# prototipo_final_2_1.net
KiCad netlist of a schematic drawn in EAGLE
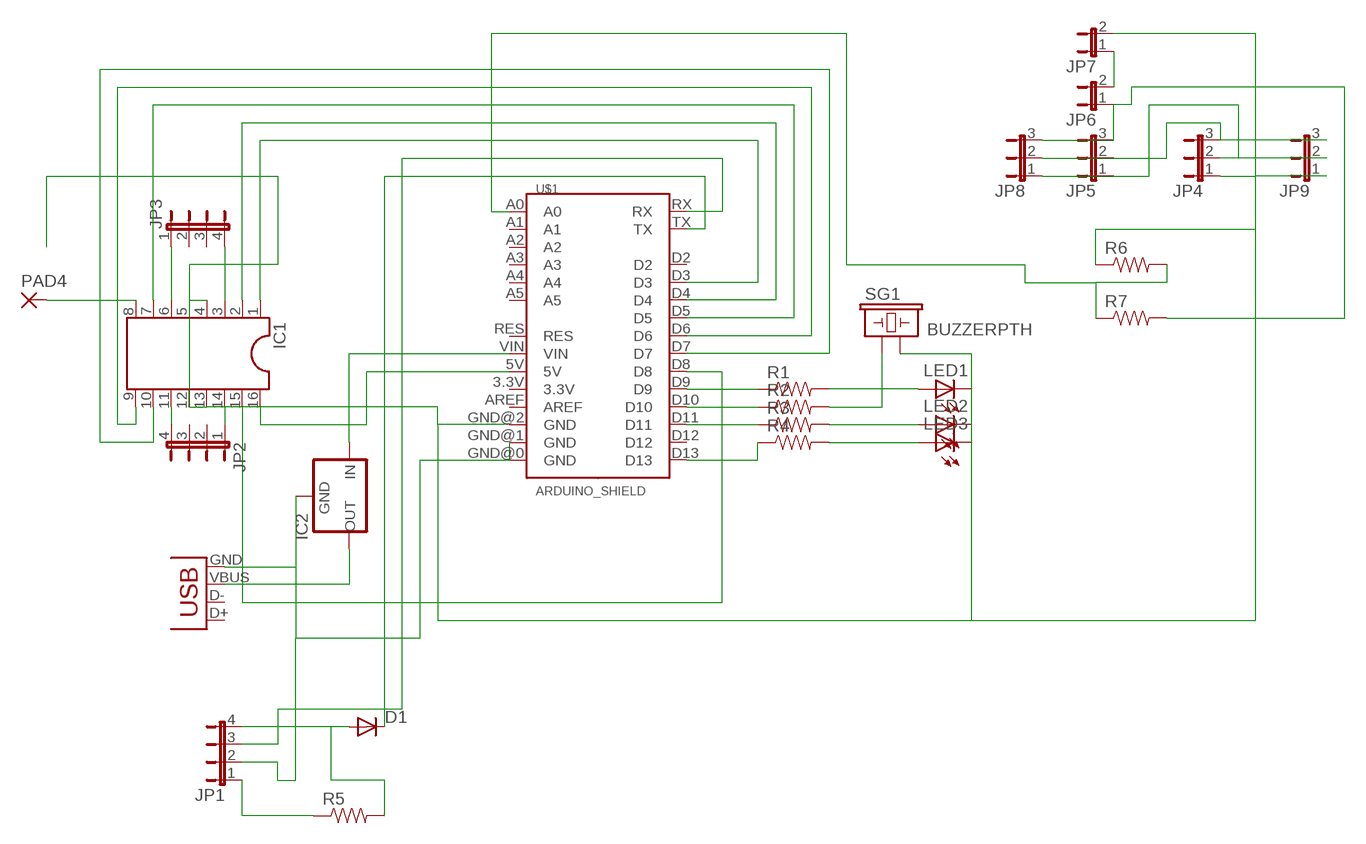
[diagram p0: schematic, sheet 1]

(export (version "E")
  (design (tool "Eeschema 10.0.6"))
  (components
    (comp (ref "D1")
      (value "DIODEPTH")
      (footprint "eagle-import:DIODE-1N4001")
      (libsource (lib "eagle-import") (part "DIODEPTH"))
    )
    (comp (ref "IC1")
      (value "DIL16S")
      (footprint "eagle-import:SOCKET-16")
      (libsource (lib "eagle-import") (part "DIL16S"))
    )
    (comp (ref "IC2")
      (value "V_REG_78XXSINK")
      (footprint "eagle-import:TO220-IGO")
      (libsource (lib "eagle-import") (part "V_REG_78XXSINK"))
    )
    (comp (ref "JP1")
      (value "JP4E")
      (footprint "eagle-import:JP4")
      (libsource (lib "eagle-import") (part "JP4E"))
    )
    (comp (ref "JP2")
      (value "JP4E")
      (footprint "eagle-import:JP4")
      (libsource (lib "eagle-import") (part "JP4E"))
    )
    (comp (ref "JP3")
      (value "JP4E")
      (footprint "eagle-import:JP4")
      (libsource (lib "eagle-import") (part "JP4E"))
    )
    (comp (ref "JP4")
      (value "JP2E")
      (footprint "eagle-import:JP2")
      (libsource (lib "eagle-import") (part "JP2E"))
    )
    (comp (ref "JP5")
      (value "JP2E")
      (footprint "eagle-import:JP2")
      (libsource (lib "eagle-import") (part "JP2E"))
    )
    (comp (ref "JP6")
      (value "JP1E")
      (footprint "eagle-import:JP1")
      (libsource (lib "eagle-import") (part "JP1E"))
    )
    (comp (ref "JP7")
      (value "JP1E")
      (footprint "eagle-import:JP1")
      (libsource (lib "eagle-import") (part "JP1E"))
    )
    (comp (ref "JP8")
      (value "JP2E")
      (footprint "eagle-import:JP2")
      (libsource (lib "eagle-import") (part "JP2E"))
    )
    (comp (ref "JP9")
      (value "JP2E")
      (footprint "eagle-import:JP2")
      (libsource (lib "eagle-import") (part "JP2E"))
    )
    (comp (ref "LED1")
      (value "LED3MM")
      (footprint "eagle-import:LED3MM")
      (libsource (lib "eagle-import") (part "LED3MM"))
    )
    (comp (ref "LED2")
      (value "LED3MM")
      (footprint "eagle-import:LED3MM")
      (libsource (lib "eagle-import") (part "LED3MM"))
    )
    (comp (ref "LED3")
      (value "LED3MM")
      (footprint "eagle-import:LED3MM")
      (libsource (lib "eagle-import") (part "LED3MM"))
    )
    (comp (ref "PAD4")
      (value "2,15/1,0")
      (footprint "eagle-import:2,15_1,0")
      (libsource (lib "eagle-import") (part "2,15/1,0"))
    )
    (comp (ref "R1")
      (value "RESISTORPTH1")
      (footprint "eagle-import:AXIAL-0.3")
      (libsource (lib "eagle-import") (part "RESISTORPTH1"))
    )
    (comp (ref "R2")
      (value "RESISTORPTH1")
      (footprint "eagle-import:AXIAL-0.3")
      (libsource (lib "eagle-import") (part "RESISTORPTH1"))
    )
    (comp (ref "R3")
      (value "RESISTORPTH1")
      (footprint "eagle-import:AXIAL-0.3")
      (libsource (lib "eagle-import") (part "RESISTORPTH1"))
    )
    (comp (ref "R4")
      (value "RESISTORPTH1")
      (footprint "eagle-import:AXIAL-0.3")
      (libsource (lib "eagle-import") (part "RESISTORPTH1"))
    )
    (comp (ref "R5")
      (value "RESISTORPTH1")
      (footprint "eagle-import:AXIAL-0.3")
      (libsource (lib "eagle-import") (part "RESISTORPTH1"))
    )
    (comp (ref "R6")
      (value "RESISTORPTH1")
      (footprint "eagle-import:AXIAL-0.3")
      (libsource (lib "eagle-import") (part "RESISTORPTH1"))
    )
    (comp (ref "R7")
      (value "RESISTORPTH1")
      (footprint "eagle-import:AXIAL-0.3")
      (libsource (lib "eagle-import") (part "RESISTORPTH1"))
    )
    (comp (ref "SG1")
      (value "BUZZERPTH")
      (footprint "eagle-import:BUZZER-12MM")
      (libsource (lib "eagle-import") (part "BUZZERPTH"))
    )
    (comp (ref "U$1")
      (value "ARDUINO_SHIELD")
      (footprint "eagle-import:DUEMILANOVE_SHIELD")
      (libsource (lib "eagle-import") (part "ARDUINO_SHIELD"))
    )
    (comp (ref "X1")
      (value "USB-A-S")
      (footprint "eagle-import:USB-A-S")
      (libsource (lib "eagle-import") (part "USB-A-S"))
    )
  )
  (nets
    (net (code "1") (name "Net-(D1-PadC)") (class "Default")
      (node (ref "D1") (pin "C") (pinfunction "C_C") (pintype "passive"))
      (node (ref "U$1") (pin "TX") (pinfunction "TX_TX") (pintype "bidirectional"))
    )
    (net (code "2") (name "Net-(IC1-Pad1)") (class "Default")
      (node (ref "IC1") (pin "1") (pinfunction "1_1") (pintype "passive"))
      (node (ref "U$1") (pin "D3") (pinfunction "D3_D3") (pintype "bidirectional"))
    )
    (net (code "3") (name "Net-(IC1-Pad2)") (class "Default")
      (node (ref "IC1") (pin "2") (pinfunction "2_2") (pintype "passive"))
      (node (ref "U$1") (pin "D4") (pinfunction "D4_D4") (pintype "bidirectional"))
    )
    (net (code "4") (name "Net-(IC1-Pad3)") (class "Default")
      (node (ref "IC1") (pin "3") (pinfunction "3_3") (pintype "passive"))
      (node (ref "JP3") (pin "4") (pinfunction "4_4") (pintype "passive"))
    )
    (net (code "5") (name "Net-(IC1-Pad6)") (class "Default")
      (node (ref "IC1") (pin "6") (pinfunction "6_6") (pintype "passive"))
      (node (ref "JP3") (pin "1") (pinfunction "1_1") (pintype "passive"))
    )
    (net (code "6") (name "Net-(IC1-Pad7)") (class "Default")
      (node (ref "IC1") (pin "7") (pinfunction "7_7") (pintype "passive"))
      (node (ref "U$1") (pin "D5") (pinfunction "D5_D5") (pintype "bidirectional"))
    )
    (net (code "7") (name "Net-(IC1-Pad9)") (class "Default")
      (node (ref "IC1") (pin "9") (pinfunction "9_9") (pintype "passive"))
      (node (ref "U$1") (pin "D6") (pinfunction "D6_D6") (pintype "bidirectional"))
    )
    (net (code "8") (name "Net-(IC1-Pad10)") (class "Default")
      (node (ref "IC1") (pin "10") (pinfunction "10_10") (pintype "passive"))
      (node (ref "U$1") (pin "D7") (pinfunction "D7_D7") (pintype "bidirectional"))
    )
    (net (code "9") (name "Net-(IC1-Pad11)") (class "Default")
      (node (ref "IC1") (pin "11") (pinfunction "11_11") (pintype "passive"))
      (node (ref "JP2") (pin "4") (pinfunction "4_4") (pintype "passive"))
    )
    (net (code "10") (name "Net-(IC1-Pad14)") (class "Default")
      (node (ref "IC1") (pin "14") (pinfunction "14_14") (pintype "passive"))
      (node (ref "JP2") (pin "1") (pinfunction "1_1") (pintype "passive"))
    )
    (net (code "11") (name "Net-(IC1-Pad15)") (class "Default")
      (node (ref "IC1") (pin "15") (pinfunction "15_15") (pintype "passive"))
      (node (ref "U$1") (pin "D8") (pinfunction "D8_D8") (pintype "bidirectional"))
    )
    (net (code "12") (name "Net-(IC1-Pad16)") (class "Default")
      (node (ref "IC1") (pin "16") (pinfunction "16_16") (pintype "passive"))
      (node (ref "U$1") (pin "5V") (pinfunction "5V_5V") (pintype "bidirectional"))
    )
    (net (code "13") (name "Net-(IC2-PadGND)") (class "Default")
      (node (ref "IC2") (pin "GND") (pinfunction "GND_GND") (pintype "input"))
      (node (ref "JP1") (pin "2") (pinfunction "2_2") (pintype "passive"))
      (node (ref "U$1") (pin "GND@0") (pinfunction "GND_GND@0") (pintype "bidirectional"))
      (node (ref "U$1") (pin "GND@1") (pinfunction "GND_GND@1") (pintype "bidirectional"))
      (node (ref "X1") (pin "GND") (pinfunction "GND_GND") (pintype "bidirectional"))
    )
    (net (code "14") (name "Net-(IC2-PadIN)") (class "Default")
      (node (ref "IC2") (pin "IN") (pinfunction "IN_IN") (pintype "input"))
      (node (ref "U$1") (pin "VIN") (pinfunction "VIN_VIN") (pintype "bidirectional"))
    )
    (net (code "15") (name "Net-(IC2-PadOUT)") (class "Default")
      (node (ref "IC2") (pin "OUT") (pinfunction "OUT_OUT") (pintype "output"))
      (node (ref "X1") (pin "VBUS") (pinfunction "VBUS_VBUS") (pintype "bidirectional"))
    )
    (net (code "16") (name "Net-(JP1-Pad3)") (class "Default")
      (node (ref "JP1") (pin "3") (pinfunction "3_3") (pintype "passive"))
      (node (ref "U$1") (pin "RX") (pinfunction "RX_RX") (pintype "bidirectional"))
    )
    (net (code "17") (name "Net-(JP4-Pad2)") (class "Default")
      (node (ref "JP4") (pin "2") (pinfunction "2_2") (pintype "passive"))
      (node (ref "JP5") (pin "1") (pinfunction "1_1") (pintype "passive"))
      (node (ref "JP8") (pin "1") (pinfunction "1_1") (pintype "passive"))
      (node (ref "JP9") (pin "2") (pinfunction "2_2") (pintype "passive"))
    )
    (net (code "18") (name "Net-(JP4-Pad3)") (class "Default")
      (node (ref "JP4") (pin "3") (pinfunction "3_3") (pintype "passive"))
      (node (ref "JP5") (pin "2") (pinfunction "2_2") (pintype "passive"))
      (node (ref "JP8") (pin "2") (pinfunction "2_2") (pintype "passive"))
      (node (ref "JP9") (pin "3") (pinfunction "3_3") (pintype "passive"))
    )
    (net (code "19") (name "Net-(JP6-Pad2)") (class "Default")
      (node (ref "JP6") (pin "2") (pinfunction "2_2") (pintype "passive"))
      (node (ref "JP7") (pin "1") (pinfunction "1_1") (pintype "passive"))
    )
    (net (code "20") (name "Net-(LED1-C)") (class "Default")
      (node (ref "IC1") (pin "12") (pinfunction "12_12") (pintype "passive"))
      (node (ref "IC1") (pin "13") (pinfunction "13_13") (pintype "passive"))
      (node (ref "IC1") (pin "4") (pinfunction "4_4") (pintype "passive"))
      (node (ref "IC1") (pin "5") (pinfunction "5_5") (pintype "passive"))
      (node (ref "JP4") (pin "1") (pinfunction "1_1") (pintype "passive"))
      (node (ref "JP7") (pin "2") (pinfunction "2_2") (pintype "passive"))
      (node (ref "JP9") (pin "1") (pinfunction "1_1") (pintype "passive"))
      (node (ref "LED1") (pin "K") (pinfunction "C_K") (pintype "passive"))
      (node (ref "LED2") (pin "K") (pinfunction "C_K") (pintype "passive"))
      (node (ref "LED3") (pin "K") (pinfunction "C_K") (pintype "passive"))
      (node (ref "R6") (pin "P$1") (pinfunction "1_P$1") (pintype "passive"))
      (node (ref "SG1") (pin "-") (pinfunction "2_-") (pintype "passive"))
      (node (ref "U$1") (pin "GND@2") (pinfunction "GND_GND@2") (pintype "bidirectional"))
    )
    (net (code "21") (name "Net-(PAD4-P)") (class "Default")
      (node (ref "IC1") (pin "8") (pinfunction "8_8") (pintype "passive"))
      (node (ref "PAD4") (pin "1") (pinfunction "P_1") (pintype "passive"))
    )
    (net (code "22") (name "Net-(R1-1)") (class "Default")
      (node (ref "R1") (pin "P$1") (pinfunction "1_P$1") (pintype "passive"))
      (node (ref "U$1") (pin "D9") (pinfunction "D9_D9") (pintype "bidirectional"))
    )
    (net (code "23") (name "Net-(R1-2)") (class "Default")
      (node (ref "LED1") (pin "A") (pinfunction "A_A") (pintype "passive"))
      (node (ref "R1") (pin "P$2") (pinfunction "2_P$2") (pintype "passive"))
    )
    (net (code "24") (name "Net-(R2-1)") (class "Default")
      (node (ref "R2") (pin "P$1") (pinfunction "1_P$1") (pintype "passive"))
      (node (ref "U$1") (pin "D10") (pinfunction "D10_D10") (pintype "bidirectional"))
    )
    (net (code "25") (name "Net-(R2-2)") (class "Default")
      (node (ref "R2") (pin "P$2") (pinfunction "2_P$2") (pintype "passive"))
      (node (ref "SG1") (pin "+") (pinfunction "1_+") (pintype "passive"))
    )
    (net (code "26") (name "Net-(R3-1)") (class "Default")
      (node (ref "R3") (pin "P$1") (pinfunction "1_P$1") (pintype "passive"))
      (node (ref "U$1") (pin "D11") (pinfunction "D11_D11") (pintype "bidirectional"))
    )
    (net (code "27") (name "Net-(R3-2)") (class "Default")
      (node (ref "LED2") (pin "A") (pinfunction "A_A") (pintype "passive"))
      (node (ref "R3") (pin "P$2") (pinfunction "2_P$2") (pintype "passive"))
    )
    (net (code "28") (name "Net-(R4-1)") (class "Default")
      (node (ref "R4") (pin "P$1") (pinfunction "1_P$1") (pintype "passive"))
      (node (ref "U$1") (pin "D13") (pinfunction "D13_D13") (pintype "bidirectional"))
    )
    (net (code "29") (name "Net-(R4-2)") (class "Default")
      (node (ref "LED3") (pin "A") (pinfunction "A_A") (pintype "passive"))
      (node (ref "R4") (pin "P$2") (pinfunction "2_P$2") (pintype "passive"))
    )
    (net (code "30") (name "Net-(R5-1)") (class "Default")
      (node (ref "JP1") (pin "1") (pinfunction "1_1") (pintype "passive"))
      (node (ref "R5") (pin "P$1") (pinfunction "1_P$1") (pintype "passive"))
    )
    (net (code "31") (name "Net-(R5-2)") (class "Default")
      (node (ref "D1") (pin "A") (pinfunction "A_A") (pintype "passive"))
      (node (ref "JP1") (pin "4") (pinfunction "4_4") (pintype "passive"))
      (node (ref "R5") (pin "P$2") (pinfunction "2_P$2") (pintype "passive"))
    )
    (net (code "32") (name "Net-(R6-2)") (class "Default")
      (node (ref "R6") (pin "P$2") (pinfunction "2_P$2") (pintype "passive"))
      (node (ref "R7") (pin "P$1") (pinfunction "1_P$1") (pintype "passive"))
      (node (ref "U$1") (pin "A0") (pinfunction "A0_A0") (pintype "bidirectional"))
    )
    (net (code "33") (name "Net-(R7-2)") (class "Default")
      (node (ref "JP5") (pin "3") (pinfunction "3_3") (pintype "passive"))
      (node (ref "JP6") (pin "1") (pinfunction "1_1") (pintype "passive"))
      (node (ref "JP8") (pin "3") (pinfunction "3_3") (pintype "passive"))
      (node (ref "R7") (pin "P$2") (pinfunction "2_P$2") (pintype "passive"))
    )
    (net (code "34") (name "unconnected-(JP2-Pad2)") (class "Default")
      (node (ref "JP2") (pin "2") (pinfunction "2_2") (pintype "passive"))
    )
    (net (code "35") (name "unconnected-(JP2-Pad3)") (class "Default")
      (node (ref "JP2") (pin "3") (pinfunction "3_3") (pintype "passive"))
    )
    (net (code "36") (name "unconnected-(JP3-Pad2)") (class "Default")
      (node (ref "JP3") (pin "2") (pinfunction "2_2") (pintype "passive"))
    )
    (net (code "37") (name "unconnected-(JP3-Pad3)") (class "Default")
      (node (ref "JP3") (pin "3") (pinfunction "3_3") (pintype "passive"))
    )
    (net (code "38") (name "unconnected-(U$1-Pad3.3V)") (class "Default")
      (node (ref "U$1") (pin "3.3V") (pinfunction "3.3V_3.3V") (pintype "bidirectional"))
    )
    (net (code "39") (name "unconnected-(U$1-PadA1)") (class "Default")
      (node (ref "U$1") (pin "A1") (pinfunction "A1_A1") (pintype "bidirectional"))
    )
    (net (code "40") (name "unconnected-(U$1-PadA2)") (class "Default")
      (node (ref "U$1") (pin "A2") (pinfunction "A2_A2") (pintype "bidirectional"))
    )
    (net (code "41") (name "unconnected-(U$1-PadA3)") (class "Default")
      (node (ref "U$1") (pin "A3") (pinfunction "A3_A3") (pintype "bidirectional"))
    )
    (net (code "42") (name "unconnected-(U$1-PadA4)") (class "Default")
      (node (ref "U$1") (pin "A4") (pinfunction "A4_A4") (pintype "bidirectional"))
    )
    (net (code "43") (name "unconnected-(U$1-PadA5)") (class "Default")
      (node (ref "U$1") (pin "A5") (pinfunction "A5_A5") (pintype "bidirectional"))
    )
    (net (code "44") (name "unconnected-(U$1-PadAREF)") (class "Default")
      (node (ref "U$1") (pin "AREF") (pinfunction "AREF_AREF") (pintype "bidirectional"))
    )
    (net (code "45") (name "unconnected-(U$1-PadD2)") (class "Default")
      (node (ref "U$1") (pin "D2") (pinfunction "D2_D2") (pintype "bidirectional"))
    )
    (net (code "46") (name "unconnected-(U$1-PadD12)") (class "Default")
      (node (ref "U$1") (pin "D12") (pinfunction "D12_D12") (pintype "bidirectional"))
    )
    (net (code "47") (name "unconnected-(U$1-PadRES)") (class "Default")
      (node (ref "U$1") (pin "RES") (pinfunction "RES_RES") (pintype "bidirectional"))
    )
    (net (code "48") (name "unconnected-(X1-PadD+)") (class "Default")
      (node (ref "X1") (pin "D+") (pinfunction "D+_D+") (pintype "bidirectional"))
    )
    (net (code "49") (name "unconnected-(X1-PadD-)") (class "Default")
      (node (ref "X1") (pin "D-") (pinfunction "D-_D-") (pintype "bidirectional"))
    )
  )
)
